# Clippard_8-MC_v01.net
KiCad netlist of a schematic drawn in EAGLE
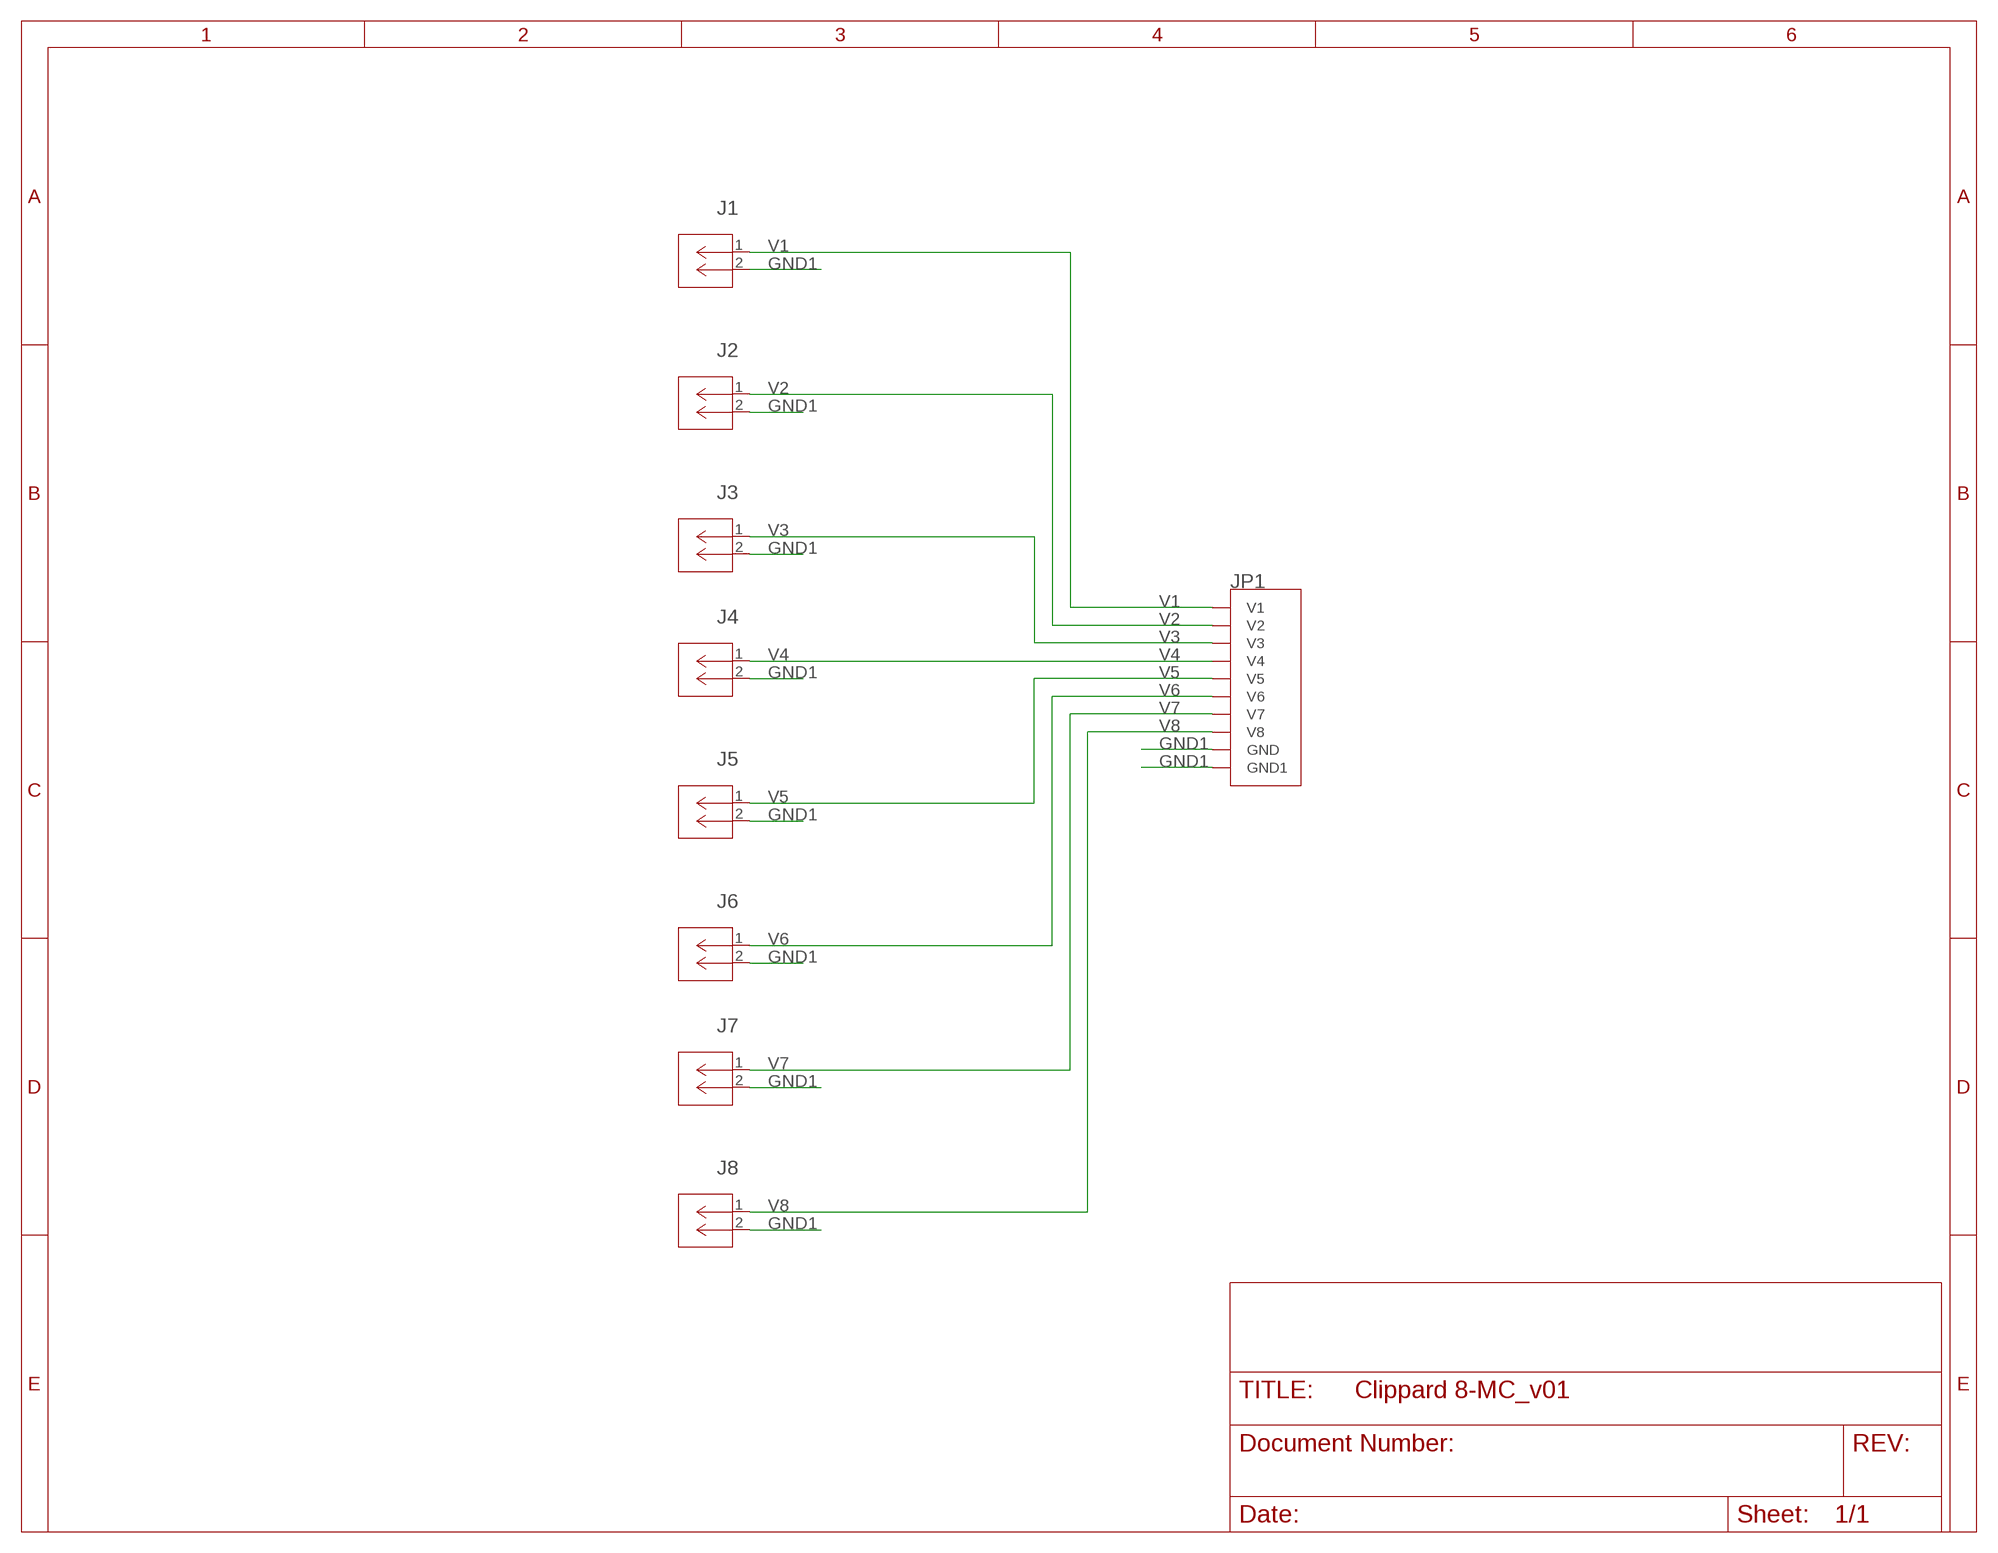
[diagram p0: schematic, sheet 1]

(export (version "E")
  (design (tool "Eeschema 10.0.6"))
  (components
    (comp (ref "J1")
      (value "MOLEX_436500215C")
      (footprint "eagle-import:MOLEX_2P_FOOTPRINT_CENTERED")
      (libsource (lib "eagle-import") (part "MOLEX_436500215C"))
    )
    (comp (ref "J2")
      (value "MOLEX_436500215C")
      (footprint "eagle-import:MOLEX_2P_FOOTPRINT_CENTERED")
      (libsource (lib "eagle-import") (part "MOLEX_436500215C"))
    )
    (comp (ref "J3")
      (value "MOLEX_436500215C")
      (footprint "eagle-import:MOLEX_2P_FOOTPRINT_CENTERED")
      (libsource (lib "eagle-import") (part "MOLEX_436500215C"))
    )
    (comp (ref "J4")
      (value "MOLEX_436500215C")
      (footprint "eagle-import:MOLEX_2P_FOOTPRINT_CENTERED")
      (libsource (lib "eagle-import") (part "MOLEX_436500215C"))
    )
    (comp (ref "J5")
      (value "MOLEX_436500215C")
      (footprint "eagle-import:MOLEX_2P_FOOTPRINT_CENTERED")
      (libsource (lib "eagle-import") (part "MOLEX_436500215C"))
    )
    (comp (ref "J6")
      (value "MOLEX_436500215C")
      (footprint "eagle-import:MOLEX_2P_FOOTPRINT_CENTERED")
      (libsource (lib "eagle-import") (part "MOLEX_436500215C"))
    )
    (comp (ref "J7")
      (value "MOLEX_436500215C")
      (footprint "eagle-import:MOLEX_2P_FOOTPRINT_CENTERED")
      (libsource (lib "eagle-import") (part "MOLEX_436500215C"))
    )
    (comp (ref "J8")
      (value "MOLEX_436500215C")
      (footprint "eagle-import:MOLEX_2P_FOOTPRINT_CENTERED")
      (libsource (lib "eagle-import") (part "MOLEX_436500215C"))
    )
    (comp (ref "JP1")
      (value "CONN_10P_TE_1761681-3C")
      (footprint "eagle-import:CONN_10P_TE_1761681-3_SE_FOR_V02_CENTERED")
      (libsource (lib "eagle-import") (part "CONN_10P_TE_1761681-3C"))
    )
  )
  (nets
    (net (code "1") (name "/GND1") (class "Default")
      (node (ref "J1") (pin "2") (pinfunction "2_2") (pintype "passive"))
      (node (ref "J2") (pin "2") (pinfunction "2_2") (pintype "passive"))
      (node (ref "J3") (pin "2") (pinfunction "2_2") (pintype "passive"))
      (node (ref "J4") (pin "2") (pinfunction "2_2") (pintype "passive"))
      (node (ref "J5") (pin "2") (pinfunction "2_2") (pintype "passive"))
      (node (ref "J6") (pin "2") (pinfunction "2_2") (pintype "passive"))
      (node (ref "J7") (pin "2") (pinfunction "2_2") (pintype "passive"))
      (node (ref "J8") (pin "2") (pinfunction "2_2") (pintype "passive"))
      (node (ref "JP1") (pin "GND") (pinfunction "GND_GND") (pintype "passive"))
      (node (ref "JP1") (pin "GND.") (pinfunction "GND1_GND.") (pintype "passive"))
    )
    (net (code "2") (name "/V1") (class "Default")
      (node (ref "J1") (pin "1") (pinfunction "1_1") (pintype "passive"))
      (node (ref "JP1") (pin "V1") (pinfunction "V1_V1") (pintype "passive"))
    )
    (net (code "3") (name "/V2") (class "Default")
      (node (ref "J2") (pin "1") (pinfunction "1_1") (pintype "passive"))
      (node (ref "JP1") (pin "V2") (pinfunction "V2_V2") (pintype "passive"))
    )
    (net (code "4") (name "/V3") (class "Default")
      (node (ref "J3") (pin "1") (pinfunction "1_1") (pintype "passive"))
      (node (ref "JP1") (pin "V3") (pinfunction "V3_V3") (pintype "passive"))
    )
    (net (code "5") (name "/V4") (class "Default")
      (node (ref "J4") (pin "1") (pinfunction "1_1") (pintype "passive"))
      (node (ref "JP1") (pin "V4") (pinfunction "V4_V4") (pintype "passive"))
    )
    (net (code "6") (name "/V5") (class "Default")
      (node (ref "J5") (pin "1") (pinfunction "1_1") (pintype "passive"))
      (node (ref "JP1") (pin "V5") (pinfunction "V5_V5") (pintype "passive"))
    )
    (net (code "7") (name "/V6") (class "Default")
      (node (ref "J6") (pin "1") (pinfunction "1_1") (pintype "passive"))
      (node (ref "JP1") (pin "V6") (pinfunction "V6_V6") (pintype "passive"))
    )
    (net (code "8") (name "/V7") (class "Default")
      (node (ref "J7") (pin "1") (pinfunction "1_1") (pintype "passive"))
      (node (ref "JP1") (pin "V7") (pinfunction "V7_V7") (pintype "passive"))
    )
    (net (code "9") (name "/V8") (class "Default")
      (node (ref "J8") (pin "1") (pinfunction "1_1") (pintype "passive"))
      (node (ref "JP1") (pin "V8") (pinfunction "V8_V8") (pintype "passive"))
    )
  )
)
